# Schemat.net
KiCad netlist of a schematic drawn in Altium Designer
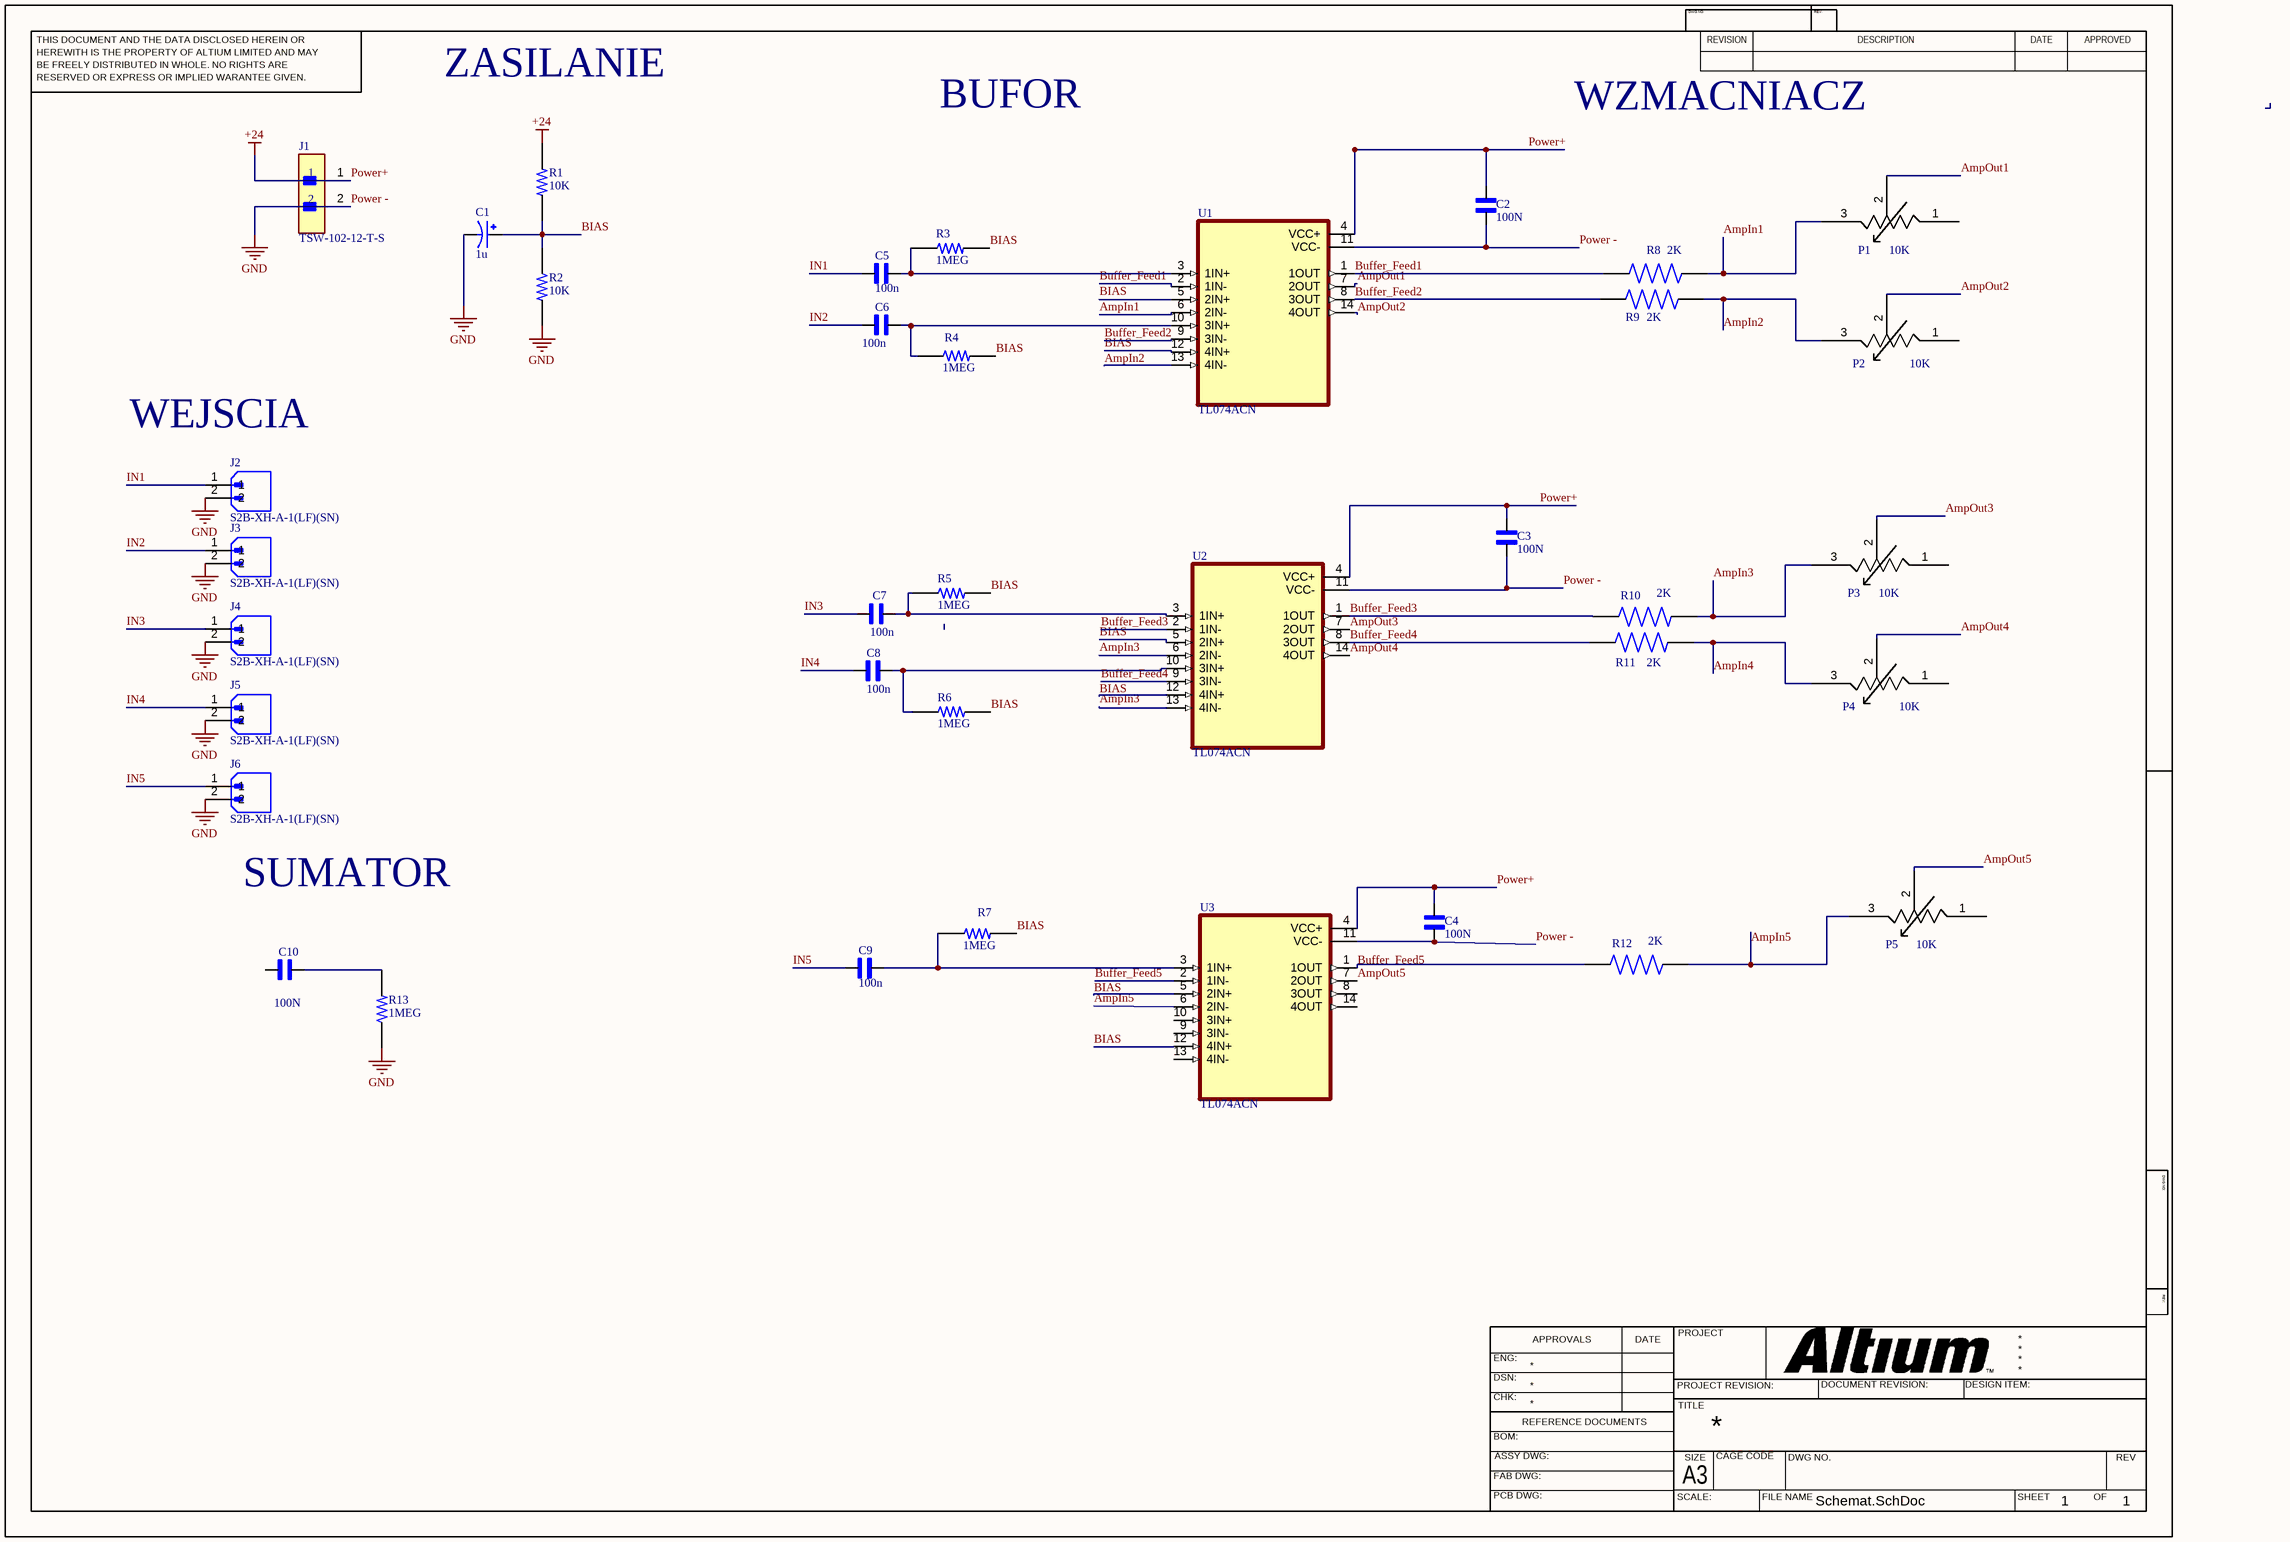
[diagram p0: Schemat.SchDoc]

(export (version "E")
  (design (tool "Eeschema 10.0.6"))
  (components
    (comp (ref "C1")
      (value "1u")
      (footprint "CAPPRD500W60D1000H2000")
      (description "10ÂµF 400V Aluminum Electrolytic Capacitors Radial, Can 2000 Hrs @ 105Â°C")
      (fields (field (name "MF") "Panasonic") (field (name "MP") "ECA2GHG100"))
      (libsource (lib "ECA2GHG100(1)") (part "ECA2GHG100"))
    )
    (comp (ref "C2")
      (value "100N")
      (footprint "CAPC4532X140N")
      (description "0.1 ÂµF Â±5% 100V Ceramic Capacitor C0G, NP0 1812 (4532 Metric)")
      (fields (field (name "MF") "KEMET") (field (name "MP") "C1812C104J1GACAUTO"))
      (libsource (lib "") (part "C1812C104J1GACAUTO_1"))
    )
    (comp (ref "C3")
      (value "100N")
      (footprint "CAPC4532X140N")
      (description "0.1 ÂµF Â±5% 100V Ceramic Capacitor C0G, NP0 1812 (4532 Metric)")
      (fields (field (name "MF") "KEMET") (field (name "MP") "C1812C104J1GACAUTO"))
      (libsource (lib "") (part "C1812C104J1GACAUTO_1"))
    )
    (comp (ref "C4")
      (value "100N")
      (footprint "CAPC4532X140N")
      (description "0.1 ÂµF Â±5% 100V Ceramic Capacitor C0G, NP0 1812 (4532 Metric)")
      (fields (field (name "MF") "KEMET") (field (name "MP") "C1812C104J1GACAUTO"))
      (libsource (lib "") (part "C1812C104J1GACAUTO_1"))
    )
    (comp (ref "C5")
      (value "100n")
      (footprint "CAPC4532X140N")
      (description "0.1 ÂµF Â±5% 100V Ceramic Capacitor C0G, NP0 1812 (4532 Metric)")
      (fields (field (name "MF") "KEMET") (field (name "MP") "C1812C104J1GACAUTO"))
      (libsource (lib "C1812C104J1GACAUTO") (part "C1812C104J1GACAUTO"))
    )
    (comp (ref "C6")
      (value "100n")
      (footprint "CAPC4532X140N")
      (description "0.1 ÂµF Â±5% 100V Ceramic Capacitor C0G, NP0 1812 (4532 Metric)")
      (fields (field (name "MF") "KEMET") (field (name "MP") "C1812C104J1GACAUTO"))
      (libsource (lib "C1812C104J1GACAUTO") (part "C1812C104J1GACAUTO"))
    )
    (comp (ref "C7")
      (value "100n")
      (footprint "CAPC4532X140N")
      (description "0.1 ÂµF Â±5% 100V Ceramic Capacitor C0G, NP0 1812 (4532 Metric)")
      (fields (field (name "MF") "KEMET") (field (name "MP") "C1812C104J1GACAUTO"))
      (libsource (lib "C1812C104J1GACAUTO") (part "C1812C104J1GACAUTO"))
    )
    (comp (ref "C8")
      (value "100n")
      (footprint "CAPC4532X140N")
      (description "0.1 ÂµF Â±5% 100V Ceramic Capacitor C0G, NP0 1812 (4532 Metric)")
      (fields (field (name "MF") "KEMET") (field (name "MP") "C1812C104J1GACAUTO"))
      (libsource (lib "C1812C104J1GACAUTO") (part "C1812C104J1GACAUTO"))
    )
    (comp (ref "C9")
      (value "100n")
      (footprint "CAPC4532X140N")
      (description "0.1 ÂµF Â±5% 100V Ceramic Capacitor C0G, NP0 1812 (4532 Metric)")
      (fields (field (name "MF") "KEMET") (field (name "MP") "C1812C104J1GACAUTO"))
      (libsource (lib "C1812C104J1GACAUTO") (part "C1812C104J1GACAUTO"))
    )
    (comp (ref "C10")
      (value "100N")
      (footprint "CAPC4532X140N")
      (description "0.1 ÂµF Â±5% 100V Ceramic Capacitor C0G, NP0 1812 (4532 Metric)")
      (fields (field (name "MF") "KEMET") (field (name "MP") "C1812C104J1GACAUTO"))
      (libsource (lib "") (part "C1812C104J1GACAUTO_2"))
    )
    (comp (ref "J1")
      (value "TSW-102-12-T-S")
      (footprint "FP-TSW-102-12-T-S-MFG")
      (description "CONN HEADER VERT 2POS 2.54MM")
      (libsource (lib "Altium Content Vault") (part "3bc925449376181038e59eaffc5286c"))
    )
    (comp (ref "J2")
      (value "S2B-XH-A-1(LF)(SN)")
      (footprint "JST_S2B-XH-A-1(LF)(SN)")
      (description "Connector Header Through Hole, Right Angle 2 position 0.098 (2.50mm)")
      (fields (field (name "MF") "JST Sales"))
      (libsource (lib "S2B-XH-A-1_LF__SN_") (part "S2B-XH-A-1(LF)(SN)"))
    )
    (comp (ref "J3")
      (value "S2B-XH-A-1(LF)(SN)")
      (footprint "JST_S2B-XH-A-1(LF)(SN)")
      (description "Connector Header Through Hole, Right Angle 2 position 0.098 (2.50mm)")
      (fields (field (name "MF") "JST Sales"))
      (libsource (lib "S2B-XH-A-1_LF__SN_") (part "S2B-XH-A-1(LF)(SN)"))
    )
    (comp (ref "J4")
      (value "S2B-XH-A-1(LF)(SN)")
      (footprint "JST_S2B-XH-A-1(LF)(SN)")
      (description "Connector Header Through Hole, Right Angle 2 position 0.098 (2.50mm)")
      (fields (field (name "MF") "JST Sales"))
      (libsource (lib "S2B-XH-A-1_LF__SN_") (part "S2B-XH-A-1(LF)(SN)"))
    )
    (comp (ref "J5")
      (value "S2B-XH-A-1(LF)(SN)")
      (footprint "JST_S2B-XH-A-1(LF)(SN)")
      (description "Connector Header Through Hole, Right Angle 2 position 0.098 (2.50mm)")
      (fields (field (name "MF") "JST Sales"))
      (libsource (lib "S2B-XH-A-1_LF__SN_") (part "S2B-XH-A-1(LF)(SN)"))
    )
    (comp (ref "J6")
      (value "S2B-XH-A-1(LF)(SN)")
      (footprint "JST_S2B-XH-A-1(LF)(SN)")
      (description "Connector Header Through Hole, Right Angle 2 position 0.098 (2.50mm)")
      (fields (field (name "MF") "JST Sales"))
      (libsource (lib "S2B-XH-A-1_LF__SN_") (part "S2B-XH-A-1(LF)(SN)"))
    )
    (comp (ref "P1")
      (value "10K")
      (footprint "16PMI-10K")
      (libsource (lib "Mixer_sche_lib") (part "16PMI-10K"))
    )
    (comp (ref "P2")
      (value "10K")
      (footprint "16PMI-10K")
      (libsource (lib "Mixer_sche_lib") (part "16PMI-10K"))
    )
    (comp (ref "P3")
      (value "10K")
      (footprint "16PMI-10K")
      (libsource (lib "Mixer_sche_lib") (part "16PMI-10K"))
    )
    (comp (ref "P4")
      (value "10K")
      (footprint "16PMI-10K")
      (libsource (lib "Mixer_sche_lib") (part "16PMI-10K"))
    )
    (comp (ref "P5")
      (value "10K")
      (footprint "16PMI-10K")
      (libsource (lib "Mixer_sche_lib") (part "16PMI-10K"))
    )
    (comp (ref "R1")
      (value "10K")
      (footprint "RESC1608X55")
      (fields
        (field (name "MF") "{'manufacturer': u'Walsin Technology Corporation'}")
        (field (name "MP") "WR06X1002FTL")
      )
      (libsource (lib "WR06X1002FTL") (part "WR06X1002FTL"))
    )
    (comp (ref "R2")
      (value "10K")
      (footprint "RESC1608X55")
      (fields
        (field (name "MF") "{'manufacturer': u'Walsin Technology Corporation'}")
        (field (name "MP") "WR06X1002FTL")
      )
      (libsource (lib "WR06X1002FTL") (part "WR06X1002FTL"))
    )
    (comp (ref "R3")
      (value "1MEG")
      (footprint "RESC1608X60N")
      (fields (field (name "MF") "Walsin Technology Corp") (field (name "MP") "WR06X1004FTL"))
      (libsource (lib "WR06X1004FTL") (part "WR06X1004FTL"))
    )
    (comp (ref "R4")
      (value "1MEG")
      (footprint "RESC1608X60N")
      (fields (field (name "MF") "Walsin Technology Corp") (field (name "MP") "WR06X1004FTL"))
      (libsource (lib "WR06X1004FTL") (part "WR06X1004FTL"))
    )
    (comp (ref "R5")
      (value "1MEG")
      (footprint "RESC1608X60N")
      (fields (field (name "MF") "Walsin Technology Corp") (field (name "MP") "WR06X1004FTL"))
      (libsource (lib "WR06X1004FTL") (part "WR06X1004FTL"))
    )
    (comp (ref "R6")
      (value "1MEG")
      (footprint "RESC1608X60N")
      (fields (field (name "MF") "Walsin Technology Corp") (field (name "MP") "WR06X1004FTL"))
      (libsource (lib "WR06X1004FTL") (part "WR06X1004FTL"))
    )
    (comp (ref "R7")
      (value "1MEG")
      (footprint "RESC1608X60N")
      (fields (field (name "MF") "Walsin Technology Corp") (field (name "MP") "WR06X1004FTL"))
      (libsource (lib "WR06X1004FTL") (part "WR06X1004FTL"))
    )
    (comp (ref "R8")
      (value "2K")
      (footprint "RES_ERJP06F2001V")
      (fields (field (name "MP") "ERJP06F2001V"))
      (libsource (lib "ERJP06F2001V") (part "ERJP06F2001V"))
    )
    (comp (ref "R9")
      (value "2K")
      (footprint "RES_ERJP06F2001V")
      (fields (field (name "MP") "ERJP06F2001V"))
      (libsource (lib "ERJP06F2001V") (part "ERJP06F2001V"))
    )
    (comp (ref "R10")
      (value "2K")
      (footprint "RES_ERJP06F2001V")
      (fields (field (name "MP") "ERJP06F2001V"))
      (libsource (lib "ERJP06F2001V") (part "ERJP06F2001V"))
    )
    (comp (ref "R11")
      (value "2K")
      (footprint "RES_ERJP06F2001V")
      (fields (field (name "MP") "ERJP06F2001V"))
      (libsource (lib "ERJP06F2001V") (part "ERJP06F2001V"))
    )
    (comp (ref "R12")
      (value "2K")
      (footprint "RES_ERJP06F2001V")
      (fields (field (name "MP") "ERJP06F2001V"))
      (libsource (lib "ERJP06F2001V") (part "ERJP06F2001V"))
    )
    (comp (ref "R13")
      (value "1MEG")
      (footprint "RESC1608X60N")
      (fields (field (name "MF") "Walsin Technology Corp") (field (name "MP") "WR06X1004FTL"))
      (libsource (lib "WR06X1004FTL") (part "WR06X1004FTL"))
    )
    (comp (ref "U1")
      (value "TL074ACN")
      (footprint "DIP794W45P254L1969H508Q14")
      (description "Quad, 30-V, 3-MHz, high slew rate (13-V/Âµs), 6-mV offset voltage, In to V+, JFET-input op amp")
      (fields (field (name "MF") "Texas Instruments"))
      (libsource (lib "TL074ACNBEST") (part "TL074ACN"))
    )
    (comp (ref "U2")
      (value "TL074ACN")
      (footprint "DIP794W45P254L1969H508Q14")
      (description "Quad, 30-V, 3-MHz, high slew rate (13-V/Âµs), 6-mV offset voltage, In to V+, JFET-input op amp")
      (fields (field (name "MF") "Texas Instruments"))
      (libsource (lib "TL074ACNBEST") (part "TL074ACN"))
    )
    (comp (ref "U3")
      (value "TL074ACN")
      (footprint "DIP794W45P254L1969H508Q14")
      (description "Quad, 30-V, 3-MHz, high slew rate (13-V/Âµs), 6-mV offset voltage, In to V+, JFET-input op amp")
      (fields (field (name "MF") "Texas Instruments"))
      (libsource (lib "TL074ACNBEST") (part "TL074ACN"))
    )
  )
  (nets
    (net (code "1") (name "+24") (class "Default")
      (node (ref "C2") (pin "2") (pinfunction "2_2") (pintype "passive"))
      (node (ref "C3") (pin "2") (pinfunction "2_2") (pintype "passive"))
      (node (ref "C4") (pin "2") (pinfunction "2_2") (pintype "passive"))
      (node (ref "J1") (pin "1") (pinfunction "1_1") (pintype "passive"))
      (node (ref "R1") (pin "1") (pinfunction "1_1") (pintype "passive"))
      (node (ref "U1") (pin "4") (pinfunction "VCC+_4") (pintype "power_in"))
      (node (ref "U2") (pin "4") (pinfunction "VCC+_4") (pintype "power_in"))
      (node (ref "U3") (pin "4") (pinfunction "VCC+_4") (pintype "power_in"))
    )
    (net (code "2") (name "/AmpIn1") (class "Default")
      (node (ref "P1") (pin "3") (pintype "passive"))
      (node (ref "R8") (pin "2") (pinfunction "2_2") (pintype "passive"))
      (node (ref "U1") (pin "6") (pinfunction "2IN-_6") (pintype "input"))
    )
    (net (code "3") (name "/AmpIn2") (class "Default")
      (node (ref "P2") (pin "3") (pintype "passive"))
      (node (ref "R9") (pin "2") (pinfunction "2_2") (pintype "passive"))
      (node (ref "U1") (pin "13") (pinfunction "4IN-_13") (pintype "input"))
    )
    (net (code "4") (name "/AmpIn3") (class "Default")
      (node (ref "P3") (pin "3") (pintype "passive"))
      (node (ref "R10") (pin "2") (pinfunction "2_2") (pintype "passive"))
      (node (ref "U2") (pin "13") (pinfunction "4IN-_13") (pintype "input"))
      (node (ref "U2") (pin "6") (pinfunction "2IN-_6") (pintype "input"))
    )
    (net (code "5") (name "/AmpIn4") (class "Default")
      (node (ref "P4") (pin "3") (pintype "passive"))
      (node (ref "R11") (pin "2") (pinfunction "2_2") (pintype "passive"))
    )
    (net (code "6") (name "/AmpIn5") (class "Default")
      (node (ref "P5") (pin "3") (pintype "passive"))
      (node (ref "R12") (pin "2") (pinfunction "2_2") (pintype "passive"))
      (node (ref "U3") (pin "6") (pinfunction "2IN-_6") (pintype "input"))
    )
    (net (code "7") (name "/AmpOut1") (class "Default")
      (node (ref "P1") (pin "2") (pintype "passive"))
      (node (ref "U1") (pin "7") (pinfunction "2OUT_7") (pintype "output"))
    )
    (net (code "8") (name "/AmpOut2") (class "Default")
      (node (ref "P2") (pin "2") (pintype "passive"))
      (node (ref "U1") (pin "14") (pinfunction "4OUT_14") (pintype "output"))
    )
    (net (code "9") (name "/AmpOut3") (class "Default")
      (node (ref "P3") (pin "2") (pintype "passive"))
      (node (ref "U2") (pin "7") (pinfunction "2OUT_7") (pintype "output"))
    )
    (net (code "10") (name "/AmpOut4") (class "Default")
      (node (ref "P4") (pin "2") (pintype "passive"))
      (node (ref "U2") (pin "14") (pinfunction "4OUT_14") (pintype "output"))
    )
    (net (code "11") (name "/AmpOut5") (class "Default")
      (node (ref "P5") (pin "2") (pintype "passive"))
      (node (ref "U3") (pin "7") (pinfunction "2OUT_7") (pintype "output"))
    )
    (net (code "12") (name "/BIAS") (class "Default")
      (node (ref "C1") (pin "P") (pinfunction "P_P") (pintype "passive"))
      (node (ref "R1") (pin "2") (pinfunction "2_2") (pintype "passive"))
      (node (ref "R2") (pin "1") (pinfunction "1_1") (pintype "passive"))
      (node (ref "R3") (pin "2") (pinfunction "2_2") (pintype "passive"))
      (node (ref "R4") (pin "2") (pinfunction "2_2") (pintype "passive"))
      (node (ref "R5") (pin "2") (pinfunction "2_2") (pintype "passive"))
      (node (ref "R6") (pin "2") (pinfunction "2_2") (pintype "passive"))
      (node (ref "R7") (pin "2") (pinfunction "2_2") (pintype "passive"))
      (node (ref "U1") (pin "12") (pinfunction "4IN+_12") (pintype "input"))
      (node (ref "U1") (pin "5") (pinfunction "2IN+_5") (pintype "input"))
      (node (ref "U2") (pin "12") (pinfunction "4IN+_12") (pintype "input"))
      (node (ref "U2") (pin "5") (pinfunction "2IN+_5") (pintype "input"))
      (node (ref "U3") (pin "12") (pinfunction "4IN+_12") (pintype "input"))
      (node (ref "U3") (pin "5") (pinfunction "2IN+_5") (pintype "input"))
    )
    (net (code "13") (name "/Buffer_Feed1") (class "Default")
      (node (ref "R8") (pin "1") (pinfunction "1_1") (pintype "passive"))
      (node (ref "U1") (pin "1") (pinfunction "1OUT_1") (pintype "output"))
      (node (ref "U1") (pin "2") (pinfunction "1IN-_2") (pintype "input"))
    )
    (net (code "14") (name "/Buffer_Feed2") (class "Default")
      (node (ref "R9") (pin "1") (pinfunction "1_1") (pintype "passive"))
      (node (ref "U1") (pin "8") (pinfunction "3OUT_8") (pintype "output"))
      (node (ref "U1") (pin "9") (pinfunction "3IN-_9") (pintype "input"))
    )
    (net (code "15") (name "/Buffer_Feed3") (class "Default")
      (node (ref "R10") (pin "1") (pinfunction "1_1") (pintype "passive"))
      (node (ref "U2") (pin "1") (pinfunction "1OUT_1") (pintype "output"))
      (node (ref "U2") (pin "2") (pinfunction "1IN-_2") (pintype "input"))
    )
    (net (code "16") (name "/Buffer_Feed4") (class "Default")
      (node (ref "R11") (pin "1") (pinfunction "1_1") (pintype "passive"))
      (node (ref "U2") (pin "8") (pinfunction "3OUT_8") (pintype "output"))
      (node (ref "U2") (pin "9") (pinfunction "3IN-_9") (pintype "input"))
    )
    (net (code "17") (name "/Buffer_Feed5") (class "Default")
      (node (ref "R12") (pin "1") (pinfunction "1_1") (pintype "passive"))
      (node (ref "U3") (pin "1") (pinfunction "1OUT_1") (pintype "output"))
      (node (ref "U3") (pin "2") (pinfunction "1IN-_2") (pintype "input"))
    )
    (net (code "18") (name "/IN1") (class "Default")
      (node (ref "C5") (pin "1") (pinfunction "1_1") (pintype "passive"))
      (node (ref "J2") (pin "1") (pinfunction "1_1") (pintype "passive"))
    )
    (net (code "19") (name "/IN2") (class "Default")
      (node (ref "C6") (pin "1") (pinfunction "1_1") (pintype "passive"))
      (node (ref "J3") (pin "1") (pinfunction "1_1") (pintype "passive"))
    )
    (net (code "20") (name "/IN3") (class "Default")
      (node (ref "C7") (pin "1") (pinfunction "1_1") (pintype "passive"))
      (node (ref "J4") (pin "1") (pinfunction "1_1") (pintype "passive"))
    )
    (net (code "21") (name "/IN4") (class "Default")
      (node (ref "C8") (pin "1") (pinfunction "1_1") (pintype "passive"))
      (node (ref "J5") (pin "1") (pinfunction "1_1") (pintype "passive"))
    )
    (net (code "22") (name "/IN5") (class "Default")
      (node (ref "C9") (pin "1") (pinfunction "1_1") (pintype "passive"))
      (node (ref "J6") (pin "1") (pinfunction "1_1") (pintype "passive"))
    )
    (net (code "23") (name "GND") (class "Default")
      (node (ref "C1") (pin "N") (pinfunction "N_N") (pintype "passive"))
      (node (ref "C2") (pin "1") (pinfunction "1_1") (pintype "passive"))
      (node (ref "C3") (pin "1") (pinfunction "1_1") (pintype "passive"))
      (node (ref "C4") (pin "1") (pinfunction "1_1") (pintype "passive"))
      (node (ref "J1") (pin "2") (pinfunction "2_2") (pintype "passive"))
      (node (ref "J2") (pin "2") (pinfunction "2_2") (pintype "passive"))
      (node (ref "J3") (pin "2") (pinfunction "2_2") (pintype "passive"))
      (node (ref "J4") (pin "2") (pinfunction "2_2") (pintype "passive"))
      (node (ref "J5") (pin "2") (pinfunction "2_2") (pintype "passive"))
      (node (ref "J6") (pin "2") (pinfunction "2_2") (pintype "passive"))
      (node (ref "R13") (pin "1") (pinfunction "1_1") (pintype "passive"))
      (node (ref "R2") (pin "2") (pinfunction "2_2") (pintype "passive"))
      (node (ref "U1") (pin "11") (pinfunction "VCC-_11") (pintype "power_in"))
      (node (ref "U2") (pin "11") (pinfunction "VCC-_11") (pintype "power_in"))
      (node (ref "U3") (pin "11") (pinfunction "VCC-_11") (pintype "power_in"))
    )
    (net (code "24") (name "Net-(C10-Pad1)") (class "Default")
      (node (ref "C10") (pin "1") (pinfunction "1_1") (pintype "passive"))
      (node (ref "R13") (pin "2") (pinfunction "2_2") (pintype "passive"))
    )
    (net (code "25") (name "Net-(U1-1IN+)") (class "Default")
      (node (ref "C5") (pin "2") (pinfunction "2_2") (pintype "passive"))
      (node (ref "R3") (pin "1") (pinfunction "1_1") (pintype "passive"))
      (node (ref "U1") (pin "3") (pinfunction "1IN+_3") (pintype "input"))
    )
    (net (code "26") (name "Net-(U1-3IN+)") (class "Default")
      (node (ref "C6") (pin "2") (pinfunction "2_2") (pintype "passive"))
      (node (ref "R4") (pin "1") (pinfunction "1_1") (pintype "passive"))
      (node (ref "U1") (pin "10") (pinfunction "3IN+_10") (pintype "input"))
    )
    (net (code "27") (name "Net-(U2-1IN+)") (class "Default")
      (node (ref "C7") (pin "2") (pinfunction "2_2") (pintype "passive"))
      (node (ref "R5") (pin "1") (pinfunction "1_1") (pintype "passive"))
      (node (ref "U2") (pin "3") (pinfunction "1IN+_3") (pintype "input"))
    )
    (net (code "28") (name "Net-(U2-3IN+)") (class "Default")
      (node (ref "C8") (pin "2") (pinfunction "2_2") (pintype "passive"))
      (node (ref "R6") (pin "1") (pinfunction "1_1") (pintype "passive"))
      (node (ref "U2") (pin "10") (pinfunction "3IN+_10") (pintype "input"))
    )
    (net (code "29") (name "Net-(U3-1IN+)") (class "Default")
      (node (ref "C9") (pin "2") (pinfunction "2_2") (pintype "passive"))
      (node (ref "R7") (pin "1") (pinfunction "1_1") (pintype "passive"))
      (node (ref "U3") (pin "3") (pinfunction "1IN+_3") (pintype "input"))
    )
    (net (code "30") (name "unconnected-(C10-Pad2)") (class "Default")
      (node (ref "C10") (pin "2") (pinfunction "2_2") (pintype "passive"))
    )
    (net (code "31") (name "unconnected-(P1-Pad1)") (class "Default")
      (node (ref "P1") (pin "1") (pintype "passive"))
    )
    (net (code "32") (name "unconnected-(P2-Pad1)") (class "Default")
      (node (ref "P2") (pin "1") (pintype "passive"))
    )
    (net (code "33") (name "unconnected-(P3-Pad1)") (class "Default")
      (node (ref "P3") (pin "1") (pintype "passive"))
    )
    (net (code "34") (name "unconnected-(P4-Pad1)") (class "Default")
      (node (ref "P4") (pin "1") (pintype "passive"))
    )
    (net (code "35") (name "unconnected-(P5-Pad1)") (class "Default")
      (node (ref "P5") (pin "1") (pintype "passive"))
    )
    (net (code "36") (name "unconnected-(U3-3IN+-Pad10)") (class "Default")
      (node (ref "U3") (pin "10") (pinfunction "3IN+_10") (pintype "input"))
    )
    (net (code "37") (name "unconnected-(U3-3IN--Pad9)") (class "Default")
      (node (ref "U3") (pin "9") (pinfunction "3IN-_9") (pintype "input"))
    )
    (net (code "38") (name "unconnected-(U3-3OUT-Pad8)") (class "Default")
      (node (ref "U3") (pin "8") (pinfunction "3OUT_8") (pintype "output"))
    )
    (net (code "39") (name "unconnected-(U3-4IN--Pad13)") (class "Default")
      (node (ref "U3") (pin "13") (pinfunction "4IN-_13") (pintype "input"))
    )
    (net (code "40") (name "unconnected-(U3-4OUT-Pad14)") (class "Default")
      (node (ref "U3") (pin "14") (pinfunction "4OUT_14") (pintype "output"))
    )
  )
)
